# TriggerBoard_v5.net
KiCad netlist of a schematic drawn in EAGLE
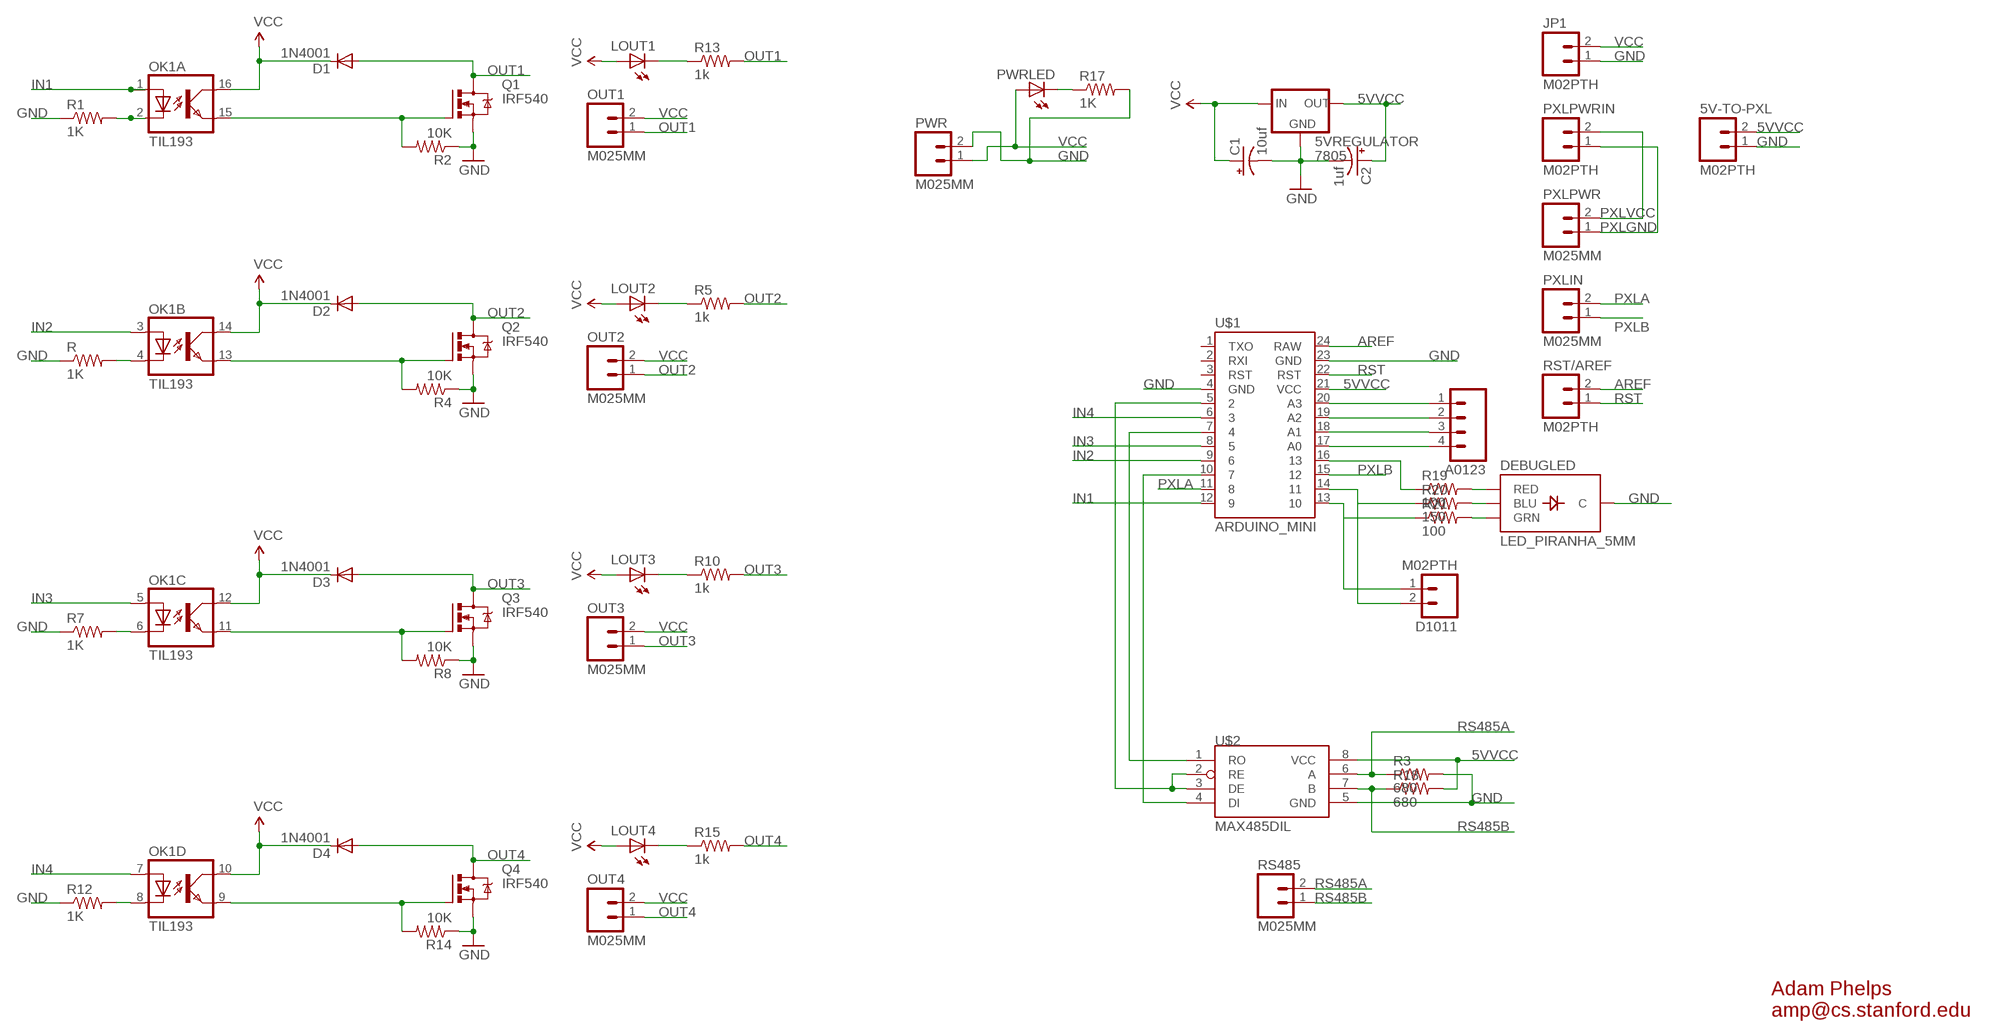
[diagram p0: schematic, sheet 1]

(export (version "E")
  (design (tool "Eeschema 10.0.6"))
  (components
    (comp (ref "5V-TO-PXL")
      (value "M02PTH")
      (footprint "eagle-import:1X02")
      (libsource (lib "eagle-import") (part "M02PTH"))
    )
    (comp (ref "5VREGULATOR")
      (value "7805")
      (footprint "eagle-import:TO220-IGO")
      (libsource (lib "eagle-import") (part "V_REG_78XXSINK"))
    )
    (comp (ref "A0123")
      (value "M04PTH")
      (footprint "eagle-import:1X04")
      (libsource (lib "eagle-import") (part "M04PTH"))
    )
    (comp (ref "C1")
      (value "10uf")
      (footprint "eagle-import:CPOL-RADIAL-10UF-25V")
      (libsource (lib "eagle-import") (part "CAP_POLPTH2"))
    )
    (comp (ref "C2")
      (value "1uf")
      (footprint "eagle-import:CPOL-RADIAL-10UF-25V")
      (libsource (lib "eagle-import") (part "CAP_POLPTH2"))
    )
    (comp (ref "D1")
      (value "1N4001")
      (footprint "eagle-import:DIODE-1N4001")
      (libsource (lib "eagle-import") (part "DIODEPTH"))
    )
    (comp (ref "D2")
      (value "1N4001")
      (footprint "eagle-import:DIODE-1N4001")
      (libsource (lib "eagle-import") (part "DIODEPTH"))
    )
    (comp (ref "D3")
      (value "1N4001")
      (footprint "eagle-import:DIODE-1N4001")
      (libsource (lib "eagle-import") (part "DIODEPTH"))
    )
    (comp (ref "D4")
      (value "1N4001")
      (footprint "eagle-import:DIODE-1N4001")
      (libsource (lib "eagle-import") (part "DIODEPTH"))
    )
    (comp (ref "D1011")
      (value "M02PTH")
      (footprint "eagle-import:1X02")
      (libsource (lib "eagle-import") (part "M02PTH"))
    )
    (comp (ref "DEBUGLED")
      (value "LED_PIRANHA_5MM")
      (footprint "eagle-import:LED_PIRANHA_5MM")
      (libsource (lib "eagle-import") (part "LED_PIRANHA_5MM"))
    )
    (comp (ref "JP1")
      (value "M02PTH")
      (footprint "eagle-import:1X02")
      (libsource (lib "eagle-import") (part "M02PTH"))
    )
    (comp (ref "LOUT1")
      (value "LED3MM")
      (footprint "eagle-import:LED3MM")
      (libsource (lib "eagle-import") (part "LED3MM"))
    )
    (comp (ref "LOUT2")
      (value "LED3MM")
      (footprint "eagle-import:LED3MM")
      (libsource (lib "eagle-import") (part "LED3MM"))
    )
    (comp (ref "LOUT3")
      (value "LED3MM")
      (footprint "eagle-import:LED3MM")
      (libsource (lib "eagle-import") (part "LED3MM"))
    )
    (comp (ref "LOUT4")
      (value "LED3MM")
      (footprint "eagle-import:LED3MM")
      (libsource (lib "eagle-import") (part "LED3MM"))
    )
    (comp (ref "OK1")
      (value "TIL193")
      (footprint "eagle-import:DIL16")
      (libsource (lib "eagle-import") (part "TIL193"))
    )
    (comp (ref "OUT1")
      (value "M025MM")
      (footprint "eagle-import:SCREWTERMINAL-5MM-2")
      (libsource (lib "eagle-import") (part "M025MM"))
    )
    (comp (ref "OUT2")
      (value "M025MM")
      (footprint "eagle-import:SCREWTERMINAL-5MM-2")
      (libsource (lib "eagle-import") (part "M025MM"))
    )
    (comp (ref "OUT3")
      (value "M025MM")
      (footprint "eagle-import:SCREWTERMINAL-5MM-2")
      (libsource (lib "eagle-import") (part "M025MM"))
    )
    (comp (ref "OUT4")
      (value "M025MM")
      (footprint "eagle-import:SCREWTERMINAL-5MM-2")
      (libsource (lib "eagle-import") (part "M025MM"))
    )
    (comp (ref "PWR")
      (value "M025MM")
      (footprint "eagle-import:SCREWTERMINAL-5MM-2")
      (libsource (lib "eagle-import") (part "M025MM"))
    )
    (comp (ref "PWRLED")
      (value "LED5MM")
      (footprint "eagle-import:LED5MM")
      (libsource (lib "eagle-import") (part "LED5MM"))
    )
    (comp (ref "PXLIN")
      (value "M025MM")
      (footprint "eagle-import:SCREWTERMINAL-5MM-2")
      (libsource (lib "eagle-import") (part "M025MM"))
    )
    (comp (ref "PXLPWR")
      (value "M025MM")
      (footprint "eagle-import:SCREWTERMINAL-5MM-2")
      (libsource (lib "eagle-import") (part "M025MM"))
    )
    (comp (ref "PXLPWRIN")
      (value "M02PTH")
      (footprint "eagle-import:1X02")
      (libsource (lib "eagle-import") (part "M02PTH"))
    )
    (comp (ref "Q1")
      (value "IRF540")
      (footprint "eagle-import:TO220BV")
      (libsource (lib "eagle-import") (part "IRF540"))
    )
    (comp (ref "Q2")
      (value "IRF540")
      (footprint "eagle-import:TO220BV")
      (libsource (lib "eagle-import") (part "IRF540"))
    )
    (comp (ref "Q3")
      (value "IRF540")
      (footprint "eagle-import:TO220BV")
      (libsource (lib "eagle-import") (part "IRF540"))
    )
    (comp (ref "Q4")
      (value "IRF540")
      (footprint "eagle-import:TO220BV")
      (libsource (lib "eagle-import") (part "IRF540"))
    )
    (comp (ref "R")
      (value "1K")
      (footprint "eagle-import:AXIAL-0.4")
      (libsource (lib "eagle-import") (part "RESISTORPTH-1/4W"))
    )
    (comp (ref "R1")
      (value "1K")
      (footprint "eagle-import:AXIAL-0.4")
      (libsource (lib "eagle-import") (part "RESISTORPTH-1/4W"))
    )
    (comp (ref "R2")
      (value "10K")
      (footprint "eagle-import:AXIAL-0.4")
      (libsource (lib "eagle-import") (part "RESISTORPTH-1/4W"))
    )
    (comp (ref "R3")
      (value "680")
      (footprint "eagle-import:AXIAL-0.4")
      (libsource (lib "eagle-import") (part "RESISTORPTH-1/4W"))
    )
    (comp (ref "R4")
      (value "10K")
      (footprint "eagle-import:AXIAL-0.4")
      (libsource (lib "eagle-import") (part "RESISTORPTH-1/4W"))
    )
    (comp (ref "R5")
      (value "1k")
      (footprint "eagle-import:AXIAL-0.4")
      (libsource (lib "eagle-import") (part "RESISTORPTH-1/4W"))
    )
    (comp (ref "R7")
      (value "1K")
      (footprint "eagle-import:AXIAL-0.4")
      (libsource (lib "eagle-import") (part "RESISTORPTH-1/4W"))
    )
    (comp (ref "R8")
      (value "10K")
      (footprint "eagle-import:AXIAL-0.4")
      (libsource (lib "eagle-import") (part "RESISTORPTH-1/4W"))
    )
    (comp (ref "R10")
      (value "1k")
      (footprint "eagle-import:AXIAL-0.4")
      (libsource (lib "eagle-import") (part "RESISTORPTH-1/4W"))
    )
    (comp (ref "R12")
      (value "1K")
      (footprint "eagle-import:AXIAL-0.4")
      (libsource (lib "eagle-import") (part "RESISTORPTH-1/4W"))
    )
    (comp (ref "R13")
      (value "1k")
      (footprint "eagle-import:AXIAL-0.4")
      (libsource (lib "eagle-import") (part "RESISTORPTH-1/4W"))
    )
    (comp (ref "R14")
      (value "10K")
      (footprint "eagle-import:AXIAL-0.4")
      (libsource (lib "eagle-import") (part "RESISTORPTH-1/4W"))
    )
    (comp (ref "R15")
      (value "1k")
      (footprint "eagle-import:AXIAL-0.4")
      (libsource (lib "eagle-import") (part "RESISTORPTH-1/4W"))
    )
    (comp (ref "R17")
      (value "1K")
      (footprint "eagle-import:AXIAL-0.4")
      (libsource (lib "eagle-import") (part "RESISTORPTH-1/4W"))
    )
    (comp (ref "R18")
      (value "680")
      (footprint "eagle-import:AXIAL-0.4")
      (libsource (lib "eagle-import") (part "RESISTORPTH-1/4W"))
    )
    (comp (ref "R19")
      (value "100")
      (footprint "eagle-import:AXIAL-0.4")
      (libsource (lib "eagle-import") (part "RESISTORPTH-1/4W"))
    )
    (comp (ref "R20")
      (value "150")
      (footprint "eagle-import:AXIAL-0.4")
      (libsource (lib "eagle-import") (part "RESISTORPTH-1/4W"))
    )
    (comp (ref "R21")
      (value "100")
      (footprint "eagle-import:AXIAL-0.4")
      (libsource (lib "eagle-import") (part "RESISTORPTH-1/4W"))
    )
    (comp (ref "RS485")
      (value "M025MM")
      (footprint "eagle-import:SCREWTERMINAL-5MM-2")
      (libsource (lib "eagle-import") (part "M025MM"))
    )
    (comp (ref "RST/AREF")
      (value "M02PTH")
      (footprint "eagle-import:1X02")
      (libsource (lib "eagle-import") (part "M02PTH"))
    )
    (comp (ref "U$1")
      (value "ARDUINO_MINI")
      (footprint "eagle-import:ARDUINO_MINI")
      (libsource (lib "eagle-import") (part "ARDUINO_MINI"))
    )
    (comp (ref "U$2")
      (value "MAX485DIL")
      (footprint "eagle-import:DIL08")
      (libsource (lib "eagle-import") (part "MAX485DIL"))
    )
  )
  (nets
    (net (code "1") (name "/5VVCC") (class "Default")
      (node (ref "5V-TO-PXL") (pin "2") (pinfunction "2_2") (pintype "passive"))
      (node (ref "5VREGULATOR") (pin "OUT") (pinfunction "OUT_OUT") (pintype "output"))
      (node (ref "C2") (pin "1") (pinfunction "+_1") (pintype "passive"))
      (node (ref "R18") (pin "P$2") (pinfunction "2_P$2") (pintype "passive"))
      (node (ref "U$1") (pin "21") (pinfunction "VCC_21") (pintype "bidirectional"))
      (node (ref "U$2") (pin "8") (pinfunction "VCC_8") (pintype "bidirectional"))
    )
    (net (code "2") (name "/AREF") (class "Default")
      (node (ref "RST/AREF") (pin "2") (pinfunction "2_2") (pintype "passive"))
      (node (ref "U$1") (pin "24") (pinfunction "RAW_24") (pintype "bidirectional"))
    )
    (net (code "3") (name "/IN1") (class "Default")
      (node (ref "OK1") (pin "1") (pinfunction "A_1") (pintype "passive"))
      (node (ref "U$1") (pin "12") (pinfunction "9_12") (pintype "bidirectional"))
    )
    (net (code "4") (name "/IN2") (class "Default")
      (node (ref "OK1") (pin "3") (pinfunction "A_3") (pintype "passive"))
      (node (ref "U$1") (pin "9") (pinfunction "6_9") (pintype "bidirectional"))
    )
    (net (code "5") (name "/IN3") (class "Default")
      (node (ref "OK1") (pin "5") (pinfunction "A_5") (pintype "passive"))
      (node (ref "U$1") (pin "8") (pinfunction "5_8") (pintype "bidirectional"))
    )
    (net (code "6") (name "/IN4") (class "Default")
      (node (ref "OK1") (pin "7") (pinfunction "A_7") (pintype "passive"))
      (node (ref "U$1") (pin "6") (pinfunction "3_6") (pintype "bidirectional"))
    )
    (net (code "7") (name "/OUT1") (class "Default")
      (node (ref "D1") (pin "A") (pinfunction "A_A") (pintype "passive"))
      (node (ref "OUT1") (pin "1") (pinfunction "1_1") (pintype "passive"))
      (node (ref "Q1") (pin "D") (pinfunction "D_D") (pintype "passive"))
      (node (ref "R13") (pin "P$2") (pinfunction "2_P$2") (pintype "passive"))
    )
    (net (code "8") (name "/OUT2") (class "Default")
      (node (ref "D2") (pin "A") (pinfunction "A_A") (pintype "passive"))
      (node (ref "OUT2") (pin "1") (pinfunction "1_1") (pintype "passive"))
      (node (ref "Q2") (pin "D") (pinfunction "D_D") (pintype "passive"))
      (node (ref "R5") (pin "P$2") (pinfunction "2_P$2") (pintype "passive"))
    )
    (net (code "9") (name "/OUT3") (class "Default")
      (node (ref "D3") (pin "A") (pinfunction "A_A") (pintype "passive"))
      (node (ref "OUT3") (pin "1") (pinfunction "1_1") (pintype "passive"))
      (node (ref "Q3") (pin "D") (pinfunction "D_D") (pintype "passive"))
      (node (ref "R10") (pin "P$2") (pinfunction "2_P$2") (pintype "passive"))
    )
    (net (code "10") (name "/OUT4") (class "Default")
      (node (ref "D4") (pin "A") (pinfunction "A_A") (pintype "passive"))
      (node (ref "OUT4") (pin "1") (pinfunction "1_1") (pintype "passive"))
      (node (ref "Q4") (pin "D") (pinfunction "D_D") (pintype "passive"))
      (node (ref "R15") (pin "P$2") (pinfunction "2_P$2") (pintype "passive"))
    )
    (net (code "11") (name "/PXLA") (class "Default")
      (node (ref "PXLIN") (pin "2") (pinfunction "2_2") (pintype "passive"))
      (node (ref "U$1") (pin "11") (pinfunction "8_11") (pintype "bidirectional"))
    )
    (net (code "12") (name "/PXLB") (class "Default")
      (node (ref "PXLIN") (pin "1") (pinfunction "1_1") (pintype "passive"))
      (node (ref "U$1") (pin "15") (pinfunction "12_15") (pintype "bidirectional"))
    )
    (net (code "13") (name "/PXLGND") (class "Default")
      (node (ref "PXLPWR") (pin "1") (pinfunction "1_1") (pintype "passive"))
      (node (ref "PXLPWRIN") (pin "1") (pinfunction "1_1") (pintype "passive"))
    )
    (net (code "14") (name "/PXLVCC") (class "Default")
      (node (ref "PXLPWR") (pin "2") (pinfunction "2_2") (pintype "passive"))
      (node (ref "PXLPWRIN") (pin "2") (pinfunction "2_2") (pintype "passive"))
    )
    (net (code "15") (name "/RS485A") (class "Default")
      (node (ref "R3") (pin "P$1") (pinfunction "1_P$1") (pintype "passive"))
      (node (ref "RS485") (pin "2") (pinfunction "2_2") (pintype "passive"))
      (node (ref "U$2") (pin "6") (pinfunction "A_6") (pintype "bidirectional"))
    )
    (net (code "16") (name "/RS485B") (class "Default")
      (node (ref "R18") (pin "P$1") (pinfunction "1_P$1") (pintype "passive"))
      (node (ref "RS485") (pin "1") (pinfunction "1_1") (pintype "passive"))
      (node (ref "U$2") (pin "7") (pinfunction "B_7") (pintype "bidirectional"))
    )
    (net (code "17") (name "/RST") (class "Default")
      (node (ref "RST/AREF") (pin "1") (pinfunction "1_1") (pintype "passive"))
      (node (ref "U$1") (pin "22") (pinfunction "RST_22") (pintype "bidirectional"))
    )
    (net (code "18") (name "GND") (class "Default")
      (node (ref "5V-TO-PXL") (pin "1") (pinfunction "1_1") (pintype "passive"))
      (node (ref "5VREGULATOR") (pin "GND") (pinfunction "GND_GND") (pintype "input"))
      (node (ref "C1") (pin "2") (pinfunction "-_2") (pintype "passive"))
      (node (ref "C2") (pin "2") (pinfunction "-_2") (pintype "passive"))
      (node (ref "DEBUGLED") (pin "-") (pinfunction "C_-") (pintype "bidirectional"))
      (node (ref "JP1") (pin "1") (pinfunction "1_1") (pintype "passive"))
      (node (ref "PWR") (pin "2") (pinfunction "2_2") (pintype "passive"))
      (node (ref "Q1") (pin "S") (pinfunction "S_S") (pintype "passive"))
      (node (ref "Q2") (pin "S") (pinfunction "S_S") (pintype "passive"))
      (node (ref "Q3") (pin "S") (pinfunction "S_S") (pintype "passive"))
      (node (ref "Q4") (pin "S") (pinfunction "S_S") (pintype "passive"))
      (node (ref "R") (pin "P$1") (pinfunction "1_P$1") (pintype "passive"))
      (node (ref "R1") (pin "P$1") (pinfunction "1_P$1") (pintype "passive"))
      (node (ref "R12") (pin "P$1") (pinfunction "1_P$1") (pintype "passive"))
      (node (ref "R14") (pin "P$1") (pinfunction "1_P$1") (pintype "passive"))
      (node (ref "R17") (pin "P$2") (pinfunction "2_P$2") (pintype "passive"))
      (node (ref "R2") (pin "P$1") (pinfunction "1_P$1") (pintype "passive"))
      (node (ref "R3") (pin "P$2") (pinfunction "2_P$2") (pintype "passive"))
      (node (ref "R4") (pin "P$1") (pinfunction "1_P$1") (pintype "passive"))
      (node (ref "R7") (pin "P$1") (pinfunction "1_P$1") (pintype "passive"))
      (node (ref "R8") (pin "P$1") (pinfunction "1_P$1") (pintype "passive"))
      (node (ref "U$1") (pin "23") (pinfunction "GND_23") (pintype "bidirectional"))
      (node (ref "U$1") (pin "4") (pinfunction "GND_4") (pintype "bidirectional"))
      (node (ref "U$2") (pin "5") (pinfunction "GND_5") (pintype "bidirectional"))
    )
    (net (code "19") (name "Net-(DEBUGLED-BLU)") (class "Default")
      (node (ref "DEBUGLED") (pin "B") (pinfunction "BLU_B") (pintype "bidirectional"))
      (node (ref "R20") (pin "P$2") (pinfunction "2_P$2") (pintype "passive"))
    )
    (net (code "20") (name "Net-(DEBUGLED-GRN)") (class "Default")
      (node (ref "DEBUGLED") (pin "G") (pinfunction "GRN_G") (pintype "bidirectional"))
      (node (ref "R21") (pin "P$2") (pinfunction "2_P$2") (pintype "passive"))
    )
    (net (code "21") (name "Net-(DEBUGLED-RED)") (class "Default")
      (node (ref "DEBUGLED") (pin "R") (pinfunction "RED_R") (pintype "bidirectional"))
      (node (ref "R19") (pin "P$2") (pinfunction "2_P$2") (pintype "passive"))
    )
    (net (code "22") (name "Net-(LOUT1-C)") (class "Default")
      (node (ref "LOUT1") (pin "K") (pinfunction "C_K") (pintype "passive"))
      (node (ref "R13") (pin "P$1") (pinfunction "1_P$1") (pintype "passive"))
    )
    (net (code "23") (name "Net-(LOUT2-C)") (class "Default")
      (node (ref "LOUT2") (pin "K") (pinfunction "C_K") (pintype "passive"))
      (node (ref "R5") (pin "P$1") (pinfunction "1_P$1") (pintype "passive"))
    )
    (net (code "24") (name "Net-(LOUT3-C)") (class "Default")
      (node (ref "LOUT3") (pin "K") (pinfunction "C_K") (pintype "passive"))
      (node (ref "R10") (pin "P$1") (pinfunction "1_P$1") (pintype "passive"))
    )
    (net (code "25") (name "Net-(LOUT4-C)") (class "Default")
      (node (ref "LOUT4") (pin "K") (pinfunction "C_K") (pintype "passive"))
      (node (ref "R15") (pin "P$1") (pinfunction "1_P$1") (pintype "passive"))
    )
    (net (code "26") (name "Net-(OK1A-C)") (class "Default")
      (node (ref "OK1") (pin "2") (pinfunction "C_2") (pintype "passive"))
      (node (ref "R1") (pin "P$2") (pinfunction "2_P$2") (pintype "passive"))
    )
    (net (code "27") (name "Net-(OK1A-EMIT)") (class "Default")
      (node (ref "OK1") (pin "15") (pinfunction "EMIT_15") (pintype "passive"))
      (node (ref "Q1") (pin "G") (pinfunction "G_G") (pintype "passive"))
      (node (ref "R2") (pin "P$2") (pinfunction "2_P$2") (pintype "passive"))
    )
    (net (code "28") (name "Net-(OK1B-C)") (class "Default")
      (node (ref "OK1") (pin "4") (pinfunction "C_4") (pintype "passive"))
      (node (ref "R") (pin "P$2") (pinfunction "2_P$2") (pintype "passive"))
    )
    (net (code "29") (name "Net-(OK1B-EMIT)") (class "Default")
      (node (ref "OK1") (pin "13") (pinfunction "EMIT_13") (pintype "passive"))
      (node (ref "Q2") (pin "G") (pinfunction "G_G") (pintype "passive"))
      (node (ref "R4") (pin "P$2") (pinfunction "2_P$2") (pintype "passive"))
    )
    (net (code "30") (name "Net-(OK1C-C)") (class "Default")
      (node (ref "OK1") (pin "6") (pinfunction "C_6") (pintype "passive"))
      (node (ref "R7") (pin "P$2") (pinfunction "2_P$2") (pintype "passive"))
    )
    (net (code "31") (name "Net-(OK1C-EMIT)") (class "Default")
      (node (ref "OK1") (pin "11") (pinfunction "EMIT_11") (pintype "passive"))
      (node (ref "Q3") (pin "G") (pinfunction "G_G") (pintype "passive"))
      (node (ref "R8") (pin "P$2") (pinfunction "2_P$2") (pintype "passive"))
    )
    (net (code "32") (name "Net-(OK1D-C)") (class "Default")
      (node (ref "OK1") (pin "8") (pinfunction "C_8") (pintype "passive"))
      (node (ref "R12") (pin "P$2") (pinfunction "2_P$2") (pintype "passive"))
    )
    (net (code "33") (name "Net-(OK1D-EMIT)") (class "Default")
      (node (ref "OK1") (pin "9") (pinfunction "EMIT_9") (pintype "passive"))
      (node (ref "Q4") (pin "G") (pinfunction "G_G") (pintype "passive"))
      (node (ref "R14") (pin "P$2") (pinfunction "2_P$2") (pintype "passive"))
    )
    (net (code "34") (name "Net-(PWRLED-C)") (class "Default")
      (node (ref "PWRLED") (pin "K") (pinfunction "C_K") (pintype "passive"))
      (node (ref "R17") (pin "P$1") (pinfunction "1_P$1") (pintype "passive"))
    )
    (net (code "35") (name "Net-(R19-1)") (class "Default")
      (node (ref "R19") (pin "P$1") (pinfunction "1_P$1") (pintype "passive"))
      (node (ref "U$1") (pin "16") (pinfunction "13_16") (pintype "bidirectional"))
    )
    (net (code "36") (name "Net-(R20-1)") (class "Default")
      (node (ref "D1011") (pin "2") (pinfunction "2_2") (pintype "passive"))
      (node (ref "R20") (pin "P$1") (pinfunction "1_P$1") (pintype "passive"))
      (node (ref "U$1") (pin "14") (pinfunction "11_14") (pintype "bidirectional"))
    )
    (net (code "37") (name "Net-(R21-1)") (class "Default")
      (node (ref "D1011") (pin "1") (pinfunction "1_1") (pintype "passive"))
      (node (ref "R21") (pin "P$1") (pinfunction "1_P$1") (pintype "passive"))
      (node (ref "U$1") (pin "13") (pinfunction "10_13") (pintype "bidirectional"))
    )
    (net (code "38") (name "Net-(U$1-2)") (class "Default")
      (node (ref "U$1") (pin "5") (pinfunction "2_5") (pintype "bidirectional"))
      (node (ref "U$2") (pin "2") (pinfunction "RE_2") (pintype "bidirectional"))
      (node (ref "U$2") (pin "3") (pinfunction "DE_3") (pintype "bidirectional"))
    )
    (net (code "39") (name "Net-(U$1-4)") (class "Default")
      (node (ref "U$1") (pin "7") (pinfunction "4_7") (pintype "bidirectional"))
      (node (ref "U$2") (pin "1") (pinfunction "RO_1") (pintype "bidirectional"))
    )
    (net (code "40") (name "Net-(U$1-7)") (class "Default")
      (node (ref "U$1") (pin "10") (pinfunction "7_10") (pintype "bidirectional"))
      (node (ref "U$2") (pin "4") (pinfunction "DI_4") (pintype "bidirectional"))
    )
    (net (code "41") (name "Net-(U$1-A0)") (class "Default")
      (node (ref "A0123") (pin "4") (pinfunction "4_4") (pintype "passive"))
      (node (ref "U$1") (pin "17") (pinfunction "A0_17") (pintype "bidirectional"))
    )
    (net (code "42") (name "Net-(U$1-A1)") (class "Default")
      (node (ref "A0123") (pin "3") (pinfunction "3_3") (pintype "passive"))
      (node (ref "U$1") (pin "18") (pinfunction "A1_18") (pintype "bidirectional"))
    )
    (net (code "43") (name "Net-(U$1-A2)") (class "Default")
      (node (ref "A0123") (pin "2") (pinfunction "2_2") (pintype "passive"))
      (node (ref "U$1") (pin "19") (pinfunction "A2_19") (pintype "bidirectional"))
    )
    (net (code "44") (name "Net-(U$1-A3)") (class "Default")
      (node (ref "A0123") (pin "1") (pinfunction "1_1") (pintype "passive"))
      (node (ref "U$1") (pin "20") (pinfunction "A3_20") (pintype "bidirectional"))
    )
    (net (code "45") (name "VCC") (class "Default")
      (node (ref "5VREGULATOR") (pin "IN") (pinfunction "IN_IN") (pintype "input"))
      (node (ref "C1") (pin "1") (pinfunction "+_1") (pintype "passive"))
      (node (ref "D1") (pin "C") (pinfunction "C_C") (pintype "passive"))
      (node (ref "D2") (pin "C") (pinfunction "C_C") (pintype "passive"))
      (node (ref "D3") (pin "C") (pinfunction "C_C") (pintype "passive"))
      (node (ref "D4") (pin "C") (pinfunction "C_C") (pintype "passive"))
      (node (ref "JP1") (pin "2") (pinfunction "2_2") (pintype "passive"))
      (node (ref "LOUT1") (pin "A") (pinfunction "A_A") (pintype "passive"))
      (node (ref "LOUT2") (pin "A") (pinfunction "A_A") (pintype "passive"))
      (node (ref "LOUT3") (pin "A") (pinfunction "A_A") (pintype "passive"))
      (node (ref "LOUT4") (pin "A") (pinfunction "A_A") (pintype "passive"))
      (node (ref "OK1") (pin "10") (pinfunction "COL_10") (pintype "passive"))
      (node (ref "OK1") (pin "12") (pinfunction "COL_12") (pintype "passive"))
      (node (ref "OK1") (pin "14") (pinfunction "COL_14") (pintype "passive"))
      (node (ref "OK1") (pin "16") (pinfunction "COL_16") (pintype "passive"))
      (node (ref "OUT1") (pin "2") (pinfunction "2_2") (pintype "passive"))
      (node (ref "OUT2") (pin "2") (pinfunction "2_2") (pintype "passive"))
      (node (ref "OUT3") (pin "2") (pinfunction "2_2") (pintype "passive"))
      (node (ref "OUT4") (pin "2") (pinfunction "2_2") (pintype "passive"))
      (node (ref "PWR") (pin "1") (pinfunction "1_1") (pintype "passive"))
      (node (ref "PWRLED") (pin "A") (pinfunction "A_A") (pintype "passive"))
    )
    (net (code "46") (name "unconnected-(U$1-RST-Pad3)") (class "Default")
      (node (ref "U$1") (pin "3") (pinfunction "RST_3") (pintype "bidirectional"))
    )
    (net (code "47") (name "unconnected-(U$1-RXI-Pad2)") (class "Default")
      (node (ref "U$1") (pin "2") (pinfunction "RXI_2") (pintype "bidirectional"))
    )
    (net (code "48") (name "unconnected-(U$1-TXO-Pad1)") (class "Default")
      (node (ref "U$1") (pin "1") (pinfunction "TXO_1") (pintype "bidirectional"))
    )
  )
)
